# carte_ultrason.net
KiCad netlist of a schematic drawn in EAGLE
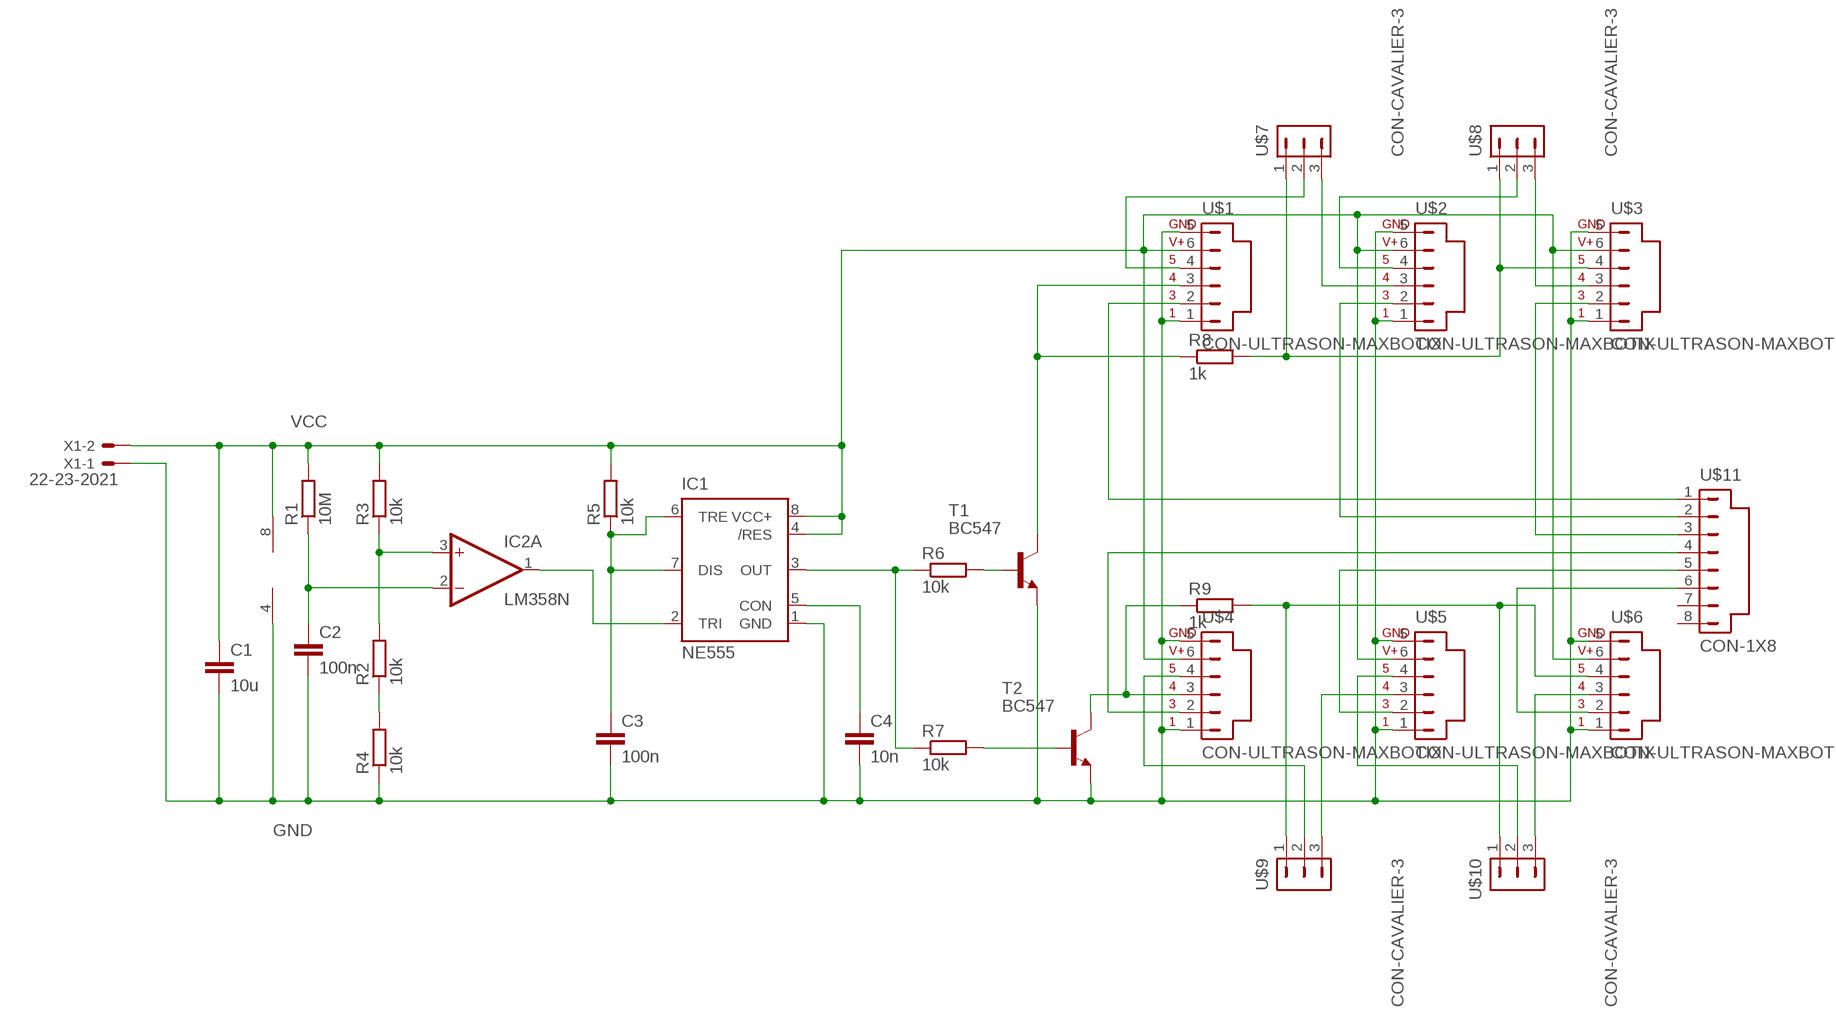
[diagram p0: schematic, sheet 1]

(export (version "E")
  (design (tool "Eeschema 10.0.6"))
  (components
    (comp (ref "C1")
      (value "10u")
      (footprint "eagle-import:C1206K")
      (libsource (lib "eagle-import") (part "C-EUC1206K"))
    )
    (comp (ref "C2")
      (value "100n")
      (footprint "eagle-import:C0805K")
      (libsource (lib "eagle-import") (part "C-EUC0805K"))
    )
    (comp (ref "C3")
      (value "100n")
      (footprint "eagle-import:C0805K")
      (libsource (lib "eagle-import") (part "C-EUC0805K"))
    )
    (comp (ref "C4")
      (value "10n")
      (footprint "eagle-import:C0805K")
      (libsource (lib "eagle-import") (part "C-EUC0805K"))
    )
    (comp (ref "IC1")
      (value "NE555")
      (footprint "eagle-import:DIL-08")
      (fields (field (name "MF") "Arrow Electronics") (field (name "MPN") "NE555N"))
      (libsource (lib "eagle-import") (part "NE555"))
    )
    (comp (ref "IC2")
      (value "LM358N")
      (footprint "eagle-import:DIL08")
      (libsource (lib "eagle-import") (part "LM358N"))
    )
    (comp (ref "R1")
      (value "10M")
      (footprint "eagle-import:R0805W")
      (libsource (lib "eagle-import") (part "R-EU_R0805W"))
    )
    (comp (ref "R2")
      (value "10k")
      (footprint "eagle-import:R0805W")
      (libsource (lib "eagle-import") (part "R-EU_R0805W"))
    )
    (comp (ref "R3")
      (value "10k")
      (footprint "eagle-import:0207_10")
      (libsource (lib "eagle-import") (part "R-EU_0207/10"))
    )
    (comp (ref "R4")
      (value "10k")
      (footprint "eagle-import:R0805W")
      (libsource (lib "eagle-import") (part "R-EU_R0805W"))
    )
    (comp (ref "R5")
      (value "10k")
      (footprint "eagle-import:R0805W")
      (libsource (lib "eagle-import") (part "R-EU_R0805W"))
    )
    (comp (ref "R6")
      (value "10k")
      (footprint "eagle-import:0207_10")
      (libsource (lib "eagle-import") (part "R-EU_0207/10"))
    )
    (comp (ref "R7")
      (value "10k")
      (footprint "eagle-import:0207_10")
      (libsource (lib "eagle-import") (part "R-EU_0207/10"))
    )
    (comp (ref "R8")
      (value "1k")
      (footprint "eagle-import:0207_10")
      (libsource (lib "eagle-import") (part "R-EU_0207/10"))
    )
    (comp (ref "R9")
      (value "1k")
      (footprint "eagle-import:R0805W")
      (libsource (lib "eagle-import") (part "R-EU_R0805W"))
    )
    (comp (ref "T1")
      (value "BC547")
      (footprint "eagle-import:TO92")
      (libsource (lib "eagle-import") (part "BC547"))
    )
    (comp (ref "T2")
      (value "BC547")
      (footprint "eagle-import:TO92")
      (libsource (lib "eagle-import") (part "BC547"))
    )
    (comp (ref "U$1")
      (value "CON-ULTRASON-MAXBOTIX")
      (footprint "eagle-import:CON-1X6")
      (libsource (lib "eagle-import") (part "CON-ULTRASON-MAXBOTIX"))
    )
    (comp (ref "U$2")
      (value "CON-ULTRASON-MAXBOTIX")
      (footprint "eagle-import:CON-1X6")
      (libsource (lib "eagle-import") (part "CON-ULTRASON-MAXBOTIX"))
    )
    (comp (ref "U$3")
      (value "CON-ULTRASON-MAXBOTIX")
      (footprint "eagle-import:CON-1X6")
      (libsource (lib "eagle-import") (part "CON-ULTRASON-MAXBOTIX"))
    )
    (comp (ref "U$4")
      (value "CON-ULTRASON-MAXBOTIX")
      (footprint "eagle-import:CON-1X6")
      (libsource (lib "eagle-import") (part "CON-ULTRASON-MAXBOTIX"))
    )
    (comp (ref "U$5")
      (value "CON-ULTRASON-MAXBOTIX")
      (footprint "eagle-import:CON-1X6")
      (libsource (lib "eagle-import") (part "CON-ULTRASON-MAXBOTIX"))
    )
    (comp (ref "U$6")
      (value "CON-ULTRASON-MAXBOTIX")
      (footprint "eagle-import:CON-1X6")
      (libsource (lib "eagle-import") (part "CON-ULTRASON-MAXBOTIX"))
    )
    (comp (ref "U$7")
      (value "CON-CAVALIER-3")
      (footprint "eagle-import:CON-CAVALIER-3")
      (libsource (lib "eagle-import") (part "CON-CAVALIER-3"))
    )
    (comp (ref "U$8")
      (value "CON-CAVALIER-3")
      (footprint "eagle-import:CON-CAVALIER-3")
      (libsource (lib "eagle-import") (part "CON-CAVALIER-3"))
    )
    (comp (ref "U$9")
      (value "CON-CAVALIER-3")
      (footprint "eagle-import:CON-CAVALIER-3")
      (libsource (lib "eagle-import") (part "CON-CAVALIER-3"))
    )
    (comp (ref "U$10")
      (value "CON-CAVALIER-3")
      (footprint "eagle-import:CON-CAVALIER-3")
      (libsource (lib "eagle-import") (part "CON-CAVALIER-3"))
    )
    (comp (ref "U$11")
      (value "CON-1X8")
      (footprint "eagle-import:CON-1X8")
      (libsource (lib "eagle-import") (part "CON-1X8"))
    )
    (comp (ref "X1")
      (value "22-23-2021")
      (footprint "eagle-import:22-23-2021")
      (fields (field (name "MF") "MOLEX"))
      (libsource (lib "eagle-import") (part "22-23-2021"))
    )
  )
  (nets
    (net (code "1") (name "/GND") (class "Default")
      (node (ref "C1") (pin "2") (pinfunction "2_2") (pintype "passive"))
      (node (ref "C2") (pin "2") (pinfunction "2_2") (pintype "passive"))
      (node (ref "C3") (pin "2") (pinfunction "2_2") (pintype "passive"))
      (node (ref "C4") (pin "2") (pinfunction "2_2") (pintype "passive"))
      (node (ref "IC1") (pin "1") (pinfunction "GND_1") (pintype "power_in"))
      (node (ref "IC2") (pin "4") (pinfunction "V-_4") (pintype "power_in"))
      (node (ref "R4") (pin "1") (pinfunction "1_1") (pintype "passive"))
      (node (ref "T1") (pin "1") (pinfunction "E_1") (pintype "passive"))
      (node (ref "T2") (pin "1") (pinfunction "E_1") (pintype "passive"))
      (node (ref "U$1") (pin "1") (pinfunction "1_1") (pintype "passive"))
      (node (ref "U$1") (pin "5") (pinfunction "GND_5") (pintype "passive"))
      (node (ref "U$2") (pin "1") (pinfunction "1_1") (pintype "passive"))
      (node (ref "U$2") (pin "5") (pinfunction "GND_5") (pintype "passive"))
      (node (ref "U$3") (pin "1") (pinfunction "1_1") (pintype "passive"))
      (node (ref "U$3") (pin "5") (pinfunction "GND_5") (pintype "passive"))
      (node (ref "U$4") (pin "1") (pinfunction "1_1") (pintype "passive"))
      (node (ref "U$4") (pin "5") (pinfunction "GND_5") (pintype "passive"))
      (node (ref "U$5") (pin "1") (pinfunction "1_1") (pintype "passive"))
      (node (ref "U$5") (pin "5") (pinfunction "GND_5") (pintype "passive"))
      (node (ref "U$6") (pin "1") (pinfunction "1_1") (pintype "passive"))
      (node (ref "U$6") (pin "5") (pinfunction "GND_5") (pintype "passive"))
      (node (ref "X1") (pin "1") (pinfunction "S_1") (pintype "passive"))
    )
    (net (code "2") (name "/VCC") (class "Default")
      (node (ref "C1") (pin "1") (pinfunction "1_1") (pintype "passive"))
      (node (ref "IC1") (pin "4") (pinfunction "/RES_4") (pintype "input"))
      (node (ref "IC1") (pin "8") (pinfunction "VCC+_8") (pintype "power_in"))
      (node (ref "IC2") (pin "8") (pinfunction "V+_8") (pintype "power_in"))
      (node (ref "R1") (pin "2") (pinfunction "2_2") (pintype "passive"))
      (node (ref "R3") (pin "2") (pinfunction "2_2") (pintype "passive"))
      (node (ref "R5") (pin "2") (pinfunction "2_2") (pintype "passive"))
      (node (ref "U$1") (pin "6") (pinfunction "V+_6") (pintype "passive"))
      (node (ref "U$2") (pin "6") (pinfunction "V+_6") (pintype "passive"))
      (node (ref "U$3") (pin "6") (pinfunction "V+_6") (pintype "passive"))
      (node (ref "U$4") (pin "6") (pinfunction "V+_6") (pintype "passive"))
      (node (ref "U$5") (pin "6") (pinfunction "V+_6") (pintype "passive"))
      (node (ref "U$6") (pin "6") (pinfunction "V+_6") (pintype "passive"))
      (node (ref "X1") (pin "2") (pinfunction "S_2") (pintype "passive"))
    )
    (net (code "3") (name "Net-(IC1-CON)") (class "Default")
      (node (ref "C4") (pin "1") (pinfunction "1_1") (pintype "passive"))
      (node (ref "IC1") (pin "5") (pinfunction "CON_5") (pintype "input"))
    )
    (net (code "4") (name "Net-(IC1-DIS)") (class "Default")
      (node (ref "C3") (pin "1") (pinfunction "1_1") (pintype "passive"))
      (node (ref "IC1") (pin "6") (pinfunction "TRE_6") (pintype "input"))
      (node (ref "IC1") (pin "7") (pinfunction "DIS_7") (pintype "input"))
      (node (ref "R5") (pin "1") (pinfunction "1_1") (pintype "passive"))
    )
    (net (code "5") (name "Net-(IC1-OUT)") (class "Default")
      (node (ref "IC1") (pin "3") (pinfunction "OUT_3") (pintype "output"))
      (node (ref "R6") (pin "1") (pinfunction "1_1") (pintype "passive"))
      (node (ref "R7") (pin "1") (pinfunction "1_1") (pintype "passive"))
    )
    (net (code "6") (name "Net-(IC1-TRI)") (class "Default")
      (node (ref "IC1") (pin "2") (pinfunction "TRI_2") (pintype "input"))
      (node (ref "IC2") (pin "1") (pinfunction "OUT_1") (pintype "output"))
    )
    (net (code "7") (name "Net-(IC2A-+IN)") (class "Default")
      (node (ref "IC2") (pin "3") (pinfunction "+IN_3") (pintype "input"))
      (node (ref "R2") (pin "2") (pinfunction "2_2") (pintype "passive"))
      (node (ref "R3") (pin "1") (pinfunction "1_1") (pintype "passive"))
    )
    (net (code "8") (name "Net-(IC2A--IN)") (class "Default")
      (node (ref "C2") (pin "1") (pinfunction "1_1") (pintype "passive"))
      (node (ref "IC2") (pin "2") (pinfunction "-IN_2") (pintype "input"))
      (node (ref "R1") (pin "1") (pinfunction "1_1") (pintype "passive"))
    )
    (net (code "9") (name "Net-(R2-Pad1)") (class "Default")
      (node (ref "R2") (pin "1") (pinfunction "1_1") (pintype "passive"))
      (node (ref "R4") (pin "2") (pinfunction "2_2") (pintype "passive"))
    )
    (net (code "10") (name "Net-(R8-Pad2)") (class "Default")
      (node (ref "R8") (pin "2") (pinfunction "2_2") (pintype "passive"))
      (node (ref "U$3") (pin "4") (pinfunction "4_4") (pintype "passive"))
      (node (ref "U$7") (pin "1") (pinfunction "1_1") (pintype "passive"))
      (node (ref "U$8") (pin "1") (pinfunction "1_1") (pintype "passive"))
    )
    (net (code "11") (name "Net-(R9-Pad2)") (class "Default")
      (node (ref "R9") (pin "2") (pinfunction "2_2") (pintype "passive"))
      (node (ref "U$10") (pin "1") (pinfunction "1_1") (pintype "passive"))
      (node (ref "U$6") (pin "4") (pinfunction "4_4") (pintype "passive"))
      (node (ref "U$9") (pin "1") (pinfunction "1_1") (pintype "passive"))
    )
    (net (code "12") (name "Net-(T1-B)") (class "Default")
      (node (ref "R6") (pin "2") (pinfunction "2_2") (pintype "passive"))
      (node (ref "T1") (pin "2") (pinfunction "B_2") (pintype "passive"))
    )
    (net (code "13") (name "Net-(T1-C)") (class "Default")
      (node (ref "R8") (pin "1") (pinfunction "1_1") (pintype "passive"))
      (node (ref "T1") (pin "3") (pinfunction "C_3") (pintype "passive"))
      (node (ref "U$1") (pin "3") (pinfunction "3_3") (pintype "passive"))
    )
    (net (code "14") (name "Net-(T2-B)") (class "Default")
      (node (ref "R7") (pin "2") (pinfunction "2_2") (pintype "passive"))
      (node (ref "T2") (pin "2") (pinfunction "B_2") (pintype "passive"))
    )
    (net (code "15") (name "Net-(T2-C)") (class "Default")
      (node (ref "R9") (pin "1") (pinfunction "1_1") (pintype "passive"))
      (node (ref "T2") (pin "3") (pinfunction "C_3") (pintype "passive"))
      (node (ref "U$4") (pin "3") (pinfunction "3_3") (pintype "passive"))
    )
    (net (code "16") (name "Net-(U$1-Pad2)") (class "Default")
      (node (ref "U$1") (pin "2") (pinfunction "2_2") (pintype "passive"))
      (node (ref "U$11") (pin "1") (pinfunction "1_1") (pintype "passive"))
    )
    (net (code "17") (name "Net-(U$1-Pad4)") (class "Default")
      (node (ref "U$1") (pin "4") (pinfunction "4_4") (pintype "passive"))
      (node (ref "U$7") (pin "2") (pinfunction "2_2") (pintype "passive"))
    )
    (net (code "18") (name "Net-(U$2-Pad3)") (class "Default")
      (node (ref "U$2") (pin "3") (pinfunction "3_3") (pintype "passive"))
      (node (ref "U$7") (pin "3") (pinfunction "3_3") (pintype "passive"))
    )
    (net (code "19") (name "Net-(U$2-Pad4)") (class "Default")
      (node (ref "U$2") (pin "4") (pinfunction "4_4") (pintype "passive"))
      (node (ref "U$8") (pin "2") (pinfunction "2_2") (pintype "passive"))
    )
    (net (code "20") (name "Net-(U$3-Pad3)") (class "Default")
      (node (ref "U$3") (pin "3") (pinfunction "3_3") (pintype "passive"))
      (node (ref "U$8") (pin "3") (pinfunction "3_3") (pintype "passive"))
    )
    (net (code "21") (name "Net-(U$4-Pad4)") (class "Default")
      (node (ref "U$4") (pin "4") (pinfunction "4_4") (pintype "passive"))
      (node (ref "U$9") (pin "2") (pinfunction "2_2") (pintype "passive"))
    )
    (net (code "22") (name "Net-(U$5-Pad3)") (class "Default")
      (node (ref "U$5") (pin "3") (pinfunction "3_3") (pintype "passive"))
      (node (ref "U$9") (pin "3") (pinfunction "3_3") (pintype "passive"))
    )
    (net (code "23") (name "Net-(U$10-Pad2)") (class "Default")
      (node (ref "U$10") (pin "2") (pinfunction "2_2") (pintype "passive"))
      (node (ref "U$5") (pin "4") (pinfunction "4_4") (pintype "passive"))
    )
    (net (code "24") (name "Net-(U$10-Pad3)") (class "Default")
      (node (ref "U$10") (pin "3") (pinfunction "3_3") (pintype "passive"))
      (node (ref "U$6") (pin "3") (pinfunction "3_3") (pintype "passive"))
    )
    (net (code "25") (name "Net-(U$11-Pad2)") (class "Default")
      (node (ref "U$11") (pin "2") (pinfunction "2_2") (pintype "passive"))
      (node (ref "U$2") (pin "2") (pinfunction "2_2") (pintype "passive"))
    )
    (net (code "26") (name "Net-(U$11-Pad3)") (class "Default")
      (node (ref "U$11") (pin "3") (pinfunction "3_3") (pintype "passive"))
      (node (ref "U$3") (pin "2") (pinfunction "2_2") (pintype "passive"))
    )
    (net (code "27") (name "Net-(U$11-Pad4)") (class "Default")
      (node (ref "U$11") (pin "4") (pinfunction "4_4") (pintype "passive"))
      (node (ref "U$4") (pin "2") (pinfunction "2_2") (pintype "passive"))
    )
    (net (code "28") (name "Net-(U$11-Pad5)") (class "Default")
      (node (ref "U$11") (pin "5") (pinfunction "5_5") (pintype "passive"))
      (node (ref "U$5") (pin "2") (pinfunction "2_2") (pintype "passive"))
    )
    (net (code "29") (name "Net-(U$11-Pad6)") (class "Default")
      (node (ref "U$11") (pin "6") (pinfunction "6_6") (pintype "passive"))
      (node (ref "U$6") (pin "2") (pinfunction "2_2") (pintype "passive"))
    )
    (net (code "30") (name "unconnected-(U$11-Pad7)") (class "Default")
      (node (ref "U$11") (pin "7") (pinfunction "7_7") (pintype "passive"))
    )
    (net (code "31") (name "unconnected-(U$11-Pad8)") (class "Default")
      (node (ref "U$11") (pin "8") (pinfunction "8_8") (pintype "passive"))
    )
  )
)
